# Ucc_28951_Breakout.net
KiCad netlist of a schematic drawn in Altium Designer
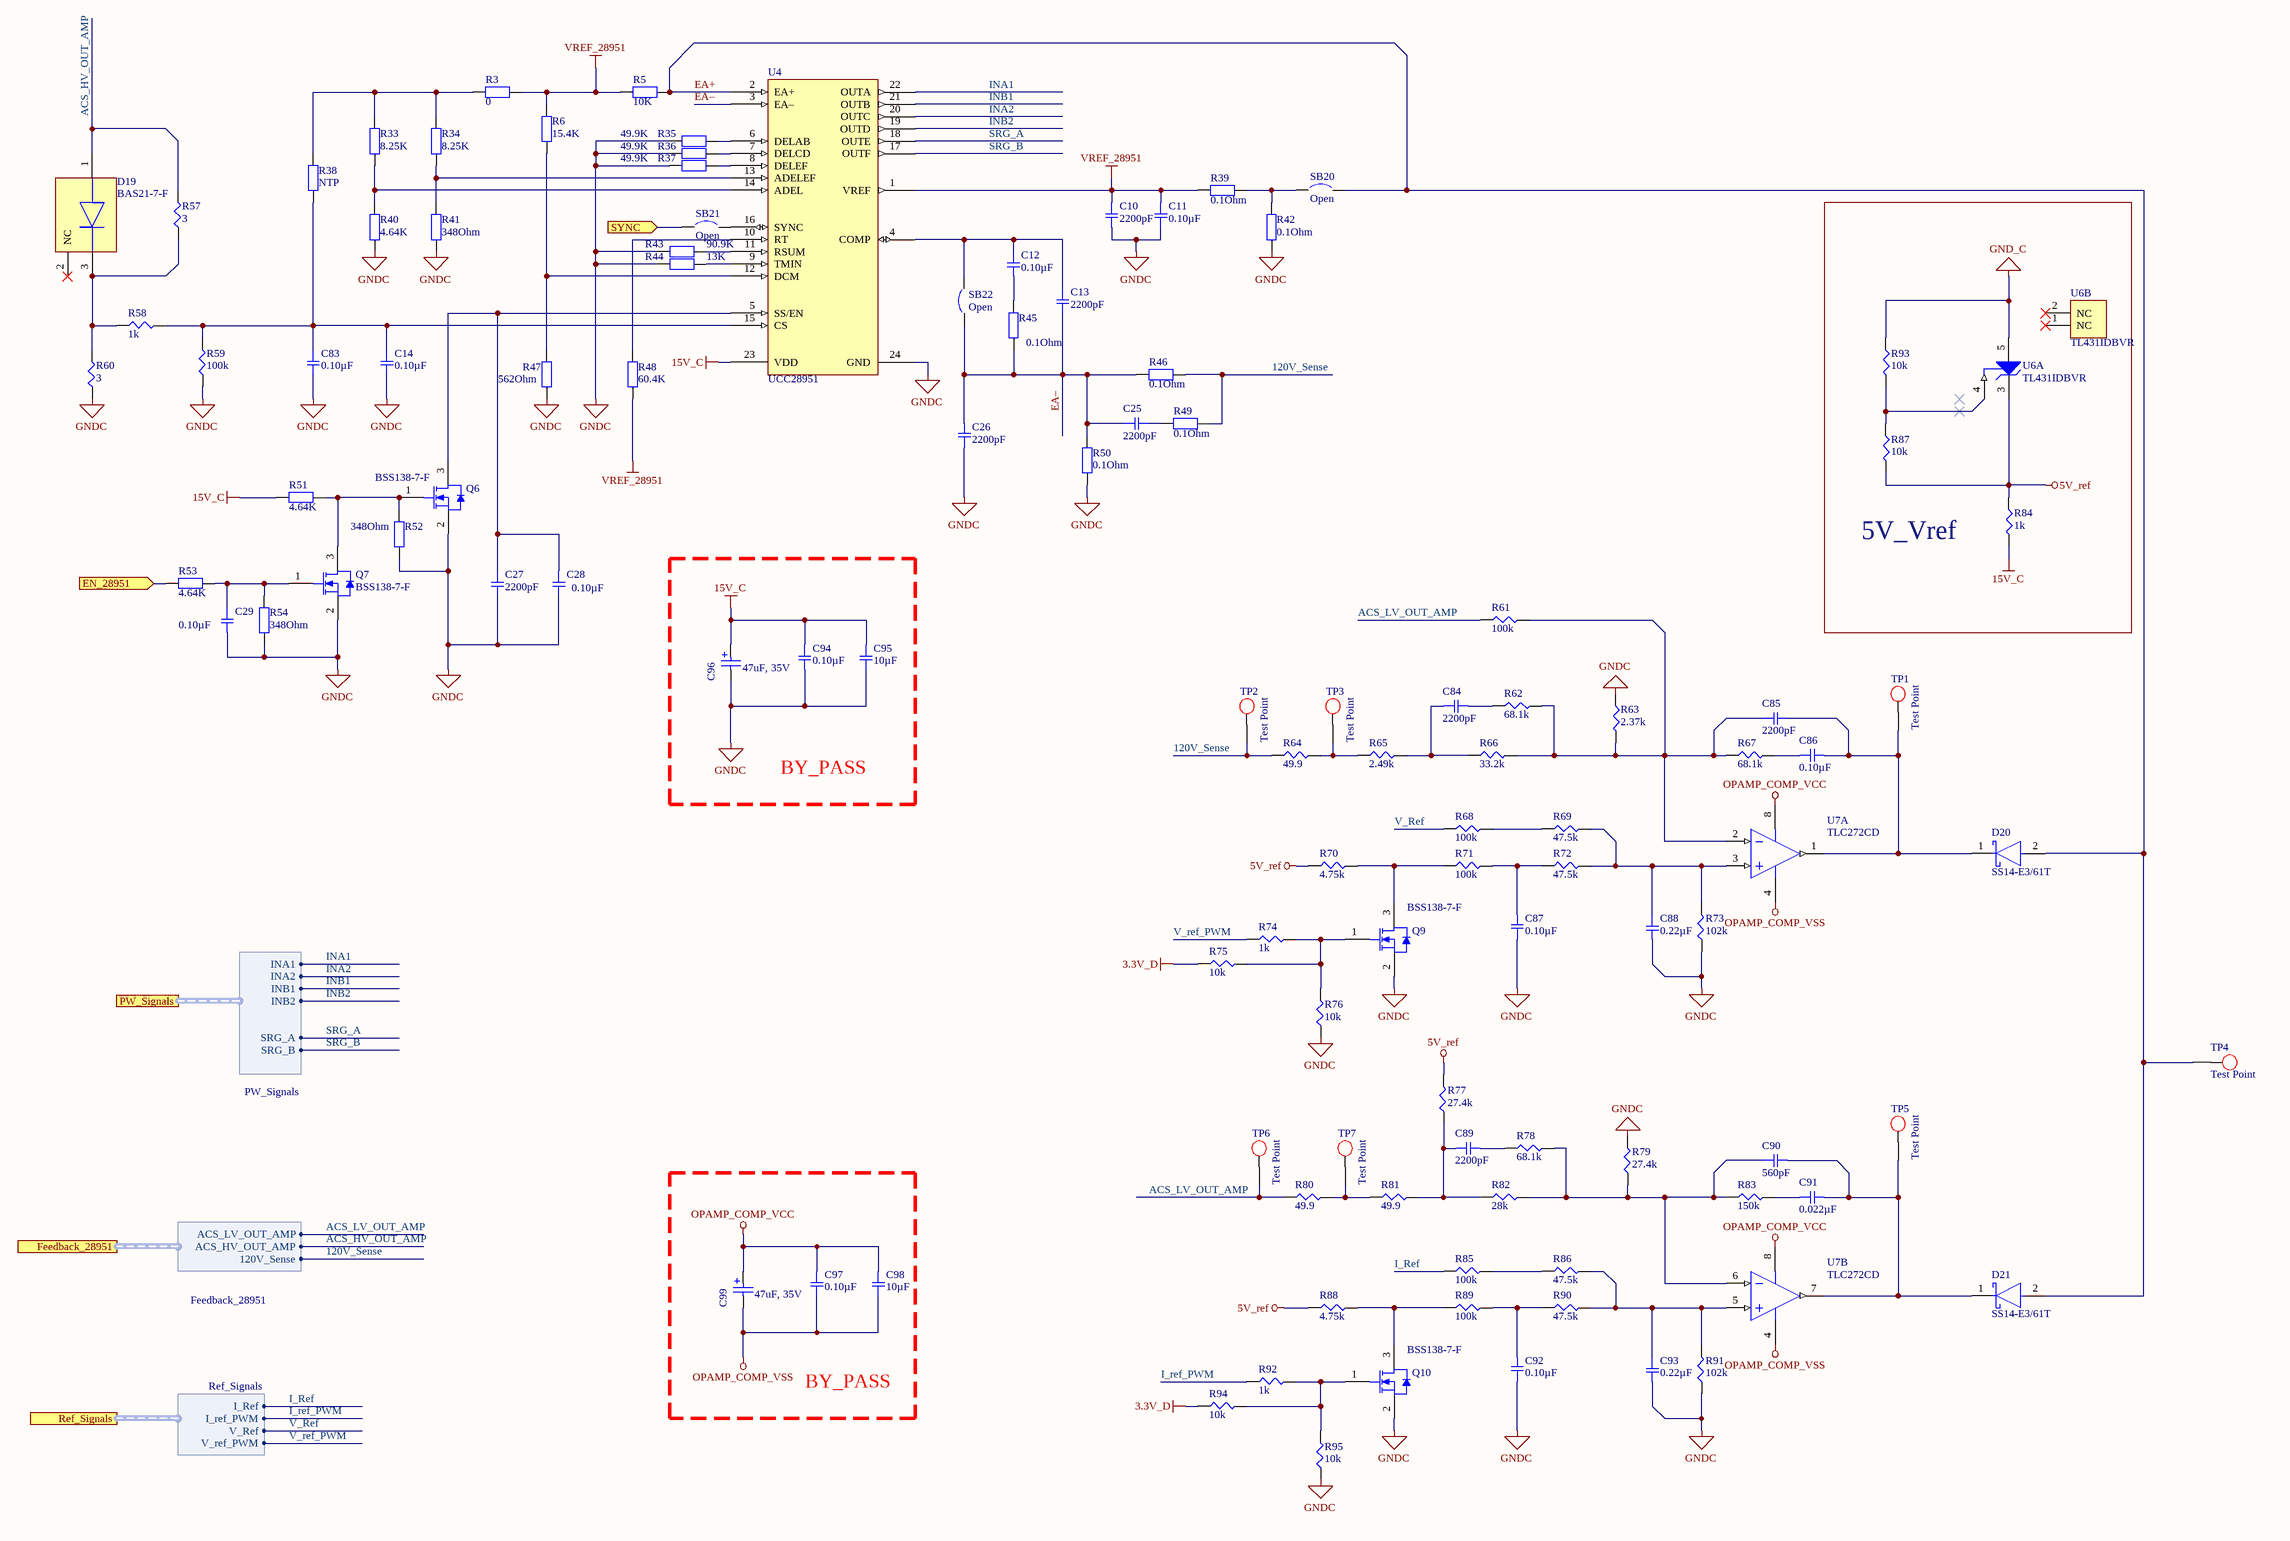
[diagram p0: Ucc_28951_Breakout.SchDoc]

(export (version "E")
  (design (tool "Eeschema 10.0.6"))
  (components
    (comp (ref "C10")
      (value "2200pF")
      (footprint "SMD-0805C")
      (description "CAP CER 2200PF 100V X7R 0805")
      (fields
        (field (name "DIGI-KEY PART NUMBER") "490-6061-1-ND")
        (field (name "PART NUMBER") "GCM216R72A222KA37D")
      )
      (libsource (lib "capacitor_murata_0805") (part "GCM216R72A222KA37D"))
    )
    (comp (ref "C11")
      (value "0.10µF")
      (footprint "SMD-0805C")
      (description "CAP CER 0.1UF 50V X7R 0805")
      (fields
        (field (name "DIGI-KEY PART NUMBER") "490-11955-1-ND")
        (field (name "PART NUMBER") "GCD21BR71H104KA01L")
      )
      (libsource (lib "capacitor_murata_0805") (part "GCD21BR71H104KA01L"))
    )
    (comp (ref "C12")
      (value "0.10µF")
      (footprint "SMD-0805C")
      (description "CAP CER 0.1UF 50V X7R 0805")
      (fields
        (field (name "DIGI-KEY PART NUMBER") "490-11955-1-ND")
        (field (name "PART NUMBER") "GCD21BR71H104KA01L")
      )
      (libsource (lib "capacitor_murata_0805") (part "GCD21BR71H104KA01L"))
    )
    (comp (ref "C13")
      (value "2200pF")
      (footprint "SMD-0805C")
      (description "CAP CER 2200PF 100V X7R 0805")
      (fields
        (field (name "DIGI-KEY PART NUMBER") "490-6061-1-ND")
        (field (name "PART NUMBER") "GCM216R72A222KA37D")
      )
      (libsource (lib "capacitor_murata_0805") (part "GCM216R72A222KA37D"))
    )
    (comp (ref "C14")
      (value "0.10µF")
      (footprint "SMD-0805C")
      (description "CAP CER 0.1UF 50V X7R 0805")
      (fields
        (field (name "DIGI-KEY PART NUMBER") "490-11955-1-ND")
        (field (name "PART NUMBER") "GCD21BR71H104KA01L")
      )
      (libsource (lib "capacitor_murata_0805") (part "GCD21BR71H104KA01L"))
    )
    (comp (ref "C25")
      (value "2200pF")
      (footprint "SMD-0805C")
      (description "CAP CER 2200PF 100V X7R 0805")
      (fields
        (field (name "DIGI-KEY PART NUMBER") "490-6061-1-ND")
        (field (name "PART NUMBER") "GCM216R72A222KA37D")
      )
      (libsource (lib "capacitor_murata_0805") (part "GCM216R72A222KA37D"))
    )
    (comp (ref "C26")
      (value "2200pF")
      (footprint "SMD-0805C")
      (description "CAP CER 2200PF 100V X7R 0805")
      (fields
        (field (name "DIGI-KEY PART NUMBER") "490-6061-1-ND")
        (field (name "PART NUMBER") "GCM216R72A222KA37D")
      )
      (libsource (lib "capacitor_murata_0805") (part "GCM216R72A222KA37D"))
    )
    (comp (ref "C27")
      (value "2200pF")
      (footprint "SMD-0805C")
      (description "CAP CER 2200PF 100V X7R 0805")
      (fields
        (field (name "DIGI-KEY PART NUMBER") "490-6061-1-ND")
        (field (name "PART NUMBER") "GCM216R72A222KA37D")
      )
      (libsource (lib "capacitor_murata_0805") (part "GCM216R72A222KA37D"))
    )
    (comp (ref "C28")
      (value "0.10µF")
      (footprint "SMD-0805C")
      (description "CAP CER 0.1UF 50V X7R 0805")
      (fields
        (field (name "DIGI-KEY PART NUMBER") "490-11955-1-ND")
        (field (name "PART NUMBER") "GCD21BR71H104KA01L")
      )
      (libsource (lib "capacitor_murata_0805") (part "GCD21BR71H104KA01L"))
    )
    (comp (ref "C29")
      (value "0.10µF")
      (footprint "SMD-0805C")
      (description "CAP CER 0.1UF 50V X7R 0805")
      (fields
        (field (name "DIGI-KEY PART NUMBER") "490-11955-1-ND")
        (field (name "PART NUMBER") "GCD21BR71H104KA01L")
      )
      (libsource (lib "capacitor_murata_0805") (part "GCD21BR71H104KA01L"))
    )
    (comp (ref "C83")
      (value "0.10µF")
      (footprint "SMD-0805C")
      (description "CAP CER 0.1UF 50V X7R 0805")
      (fields
        (field (name "DIGI-KEY PART NUMBER") "490-11955-1-ND")
        (field (name "PART NUMBER") "GCD21BR71H104KA01L")
      )
      (libsource (lib "capacitor_murata_0805") (part "GCD21BR71H104KA01L"))
    )
    (comp (ref "C84")
      (value "2200pF")
      (footprint "SMD-0603C")
      (description "CAP CER 2200PF 50V X7R 0603")
      (fields
        (field (name "DIGI-KEY PART NUMBER") "490-5766-1-ND")
        (field (name "PART NUMBER") "GCJ188R71H222KA01D")
      )
      (libsource (lib "capacitor_murata_0603") (part "GCJ188R71H222KA01D"))
    )
    (comp (ref "C85")
      (value "2200pF")
      (footprint "SMD-0603C")
      (description "CAP CER 2200PF 50V X7R 0603")
      (fields
        (field (name "DIGI-KEY PART NUMBER") "490-5766-1-ND")
        (field (name "PART NUMBER") "GCJ188R71H222KA01D")
      )
      (libsource (lib "capacitor_murata_0603") (part "GCJ188R71H222KA01D"))
    )
    (comp (ref "C86")
      (value "0.10µF")
      (footprint "SMD-0603C")
      (description "CAP CER 0.1UF 16V X7R 0603")
      (fields
        (field (name "DIGI-KEY PART NUMBER") "490-5796-1-ND")
        (field (name "PART NUMBER") "GCJ188R71C104KA01D")
      )
      (libsource (lib "capacitor_murata_0603") (part "GCJ188R71C104KA01D"))
    )
    (comp (ref "C87")
      (value "0.10µF")
      (footprint "SMD-0603C")
      (description "CAP CER 0.1UF 16V X7R 0603")
      (fields
        (field (name "DIGI-KEY PART NUMBER") "490-5796-1-ND")
        (field (name "PART NUMBER") "GCJ188R71C104KA01D")
      )
      (libsource (lib "capacitor_murata_0603") (part "GCJ188R71C104KA01D"))
    )
    (comp (ref "C88")
      (value "0.22µF")
      (footprint "SMD-0603C")
      (description "CAP CER 0.22UF 25V X7R 0603")
      (fields
        (field (name "DIGI-KEY PART NUMBER") "490-5797-1-ND")
        (field (name "PART NUMBER") "GCJ188R71E224KA12D")
      )
      (libsource (lib "capacitor_murata_0603") (part "GCJ188R71E224KA12D"))
    )
    (comp (ref "C89")
      (value "2200pF")
      (footprint "SMD-0603C")
      (description "CAP CER 2200PF 50V X7R 0603")
      (fields
        (field (name "DIGI-KEY PART NUMBER") "490-5766-1-ND")
        (field (name "PART NUMBER") "GCJ188R71H222KA01D")
      )
      (libsource (lib "capacitor_murata_0603") (part "GCJ188R71H222KA01D"))
    )
    (comp (ref "C90")
      (value "560pF")
      (footprint "SMD-0603C")
      (description "CAP CER 560PF 25V NP0 0603")
      (fields
        (field (name "DIGI-KEY PART NUMBER") "490-12711-1-ND")
        (field (name "PART NUMBER") "GRM1885C1E561JA01D")
      )
      (libsource (lib "capacitor_murata_0603") (part "GRM1885C1E561JA01D"))
    )
    (comp (ref "C91")
      (value "0.022µF")
      (footprint "SMD-0603C")
      (description "CAP CER 0.022UF 50V X7R 0603")
      (fields
        (field (name "DIGI-KEY PART NUMBER") "490-5851-1-ND")
        (field (name "PART NUMBER") "GCJ188R71H223KA01D")
      )
      (libsource (lib "capacitor_murata_0603") (part "GCJ188R71H223KA01D"))
    )
    (comp (ref "C92")
      (value "0.10µF")
      (footprint "SMD-0603C")
      (description "CAP CER 0.1UF 16V X7R 0603")
      (fields
        (field (name "DIGI-KEY PART NUMBER") "490-5796-1-ND")
        (field (name "PART NUMBER") "GCJ188R71C104KA01D")
      )
      (libsource (lib "capacitor_murata_0603") (part "GCJ188R71C104KA01D"))
    )
    (comp (ref "C93")
      (value "0.22µF")
      (footprint "SMD-0603C")
      (description "CAP CER 0.22UF 25V X7R 0603")
      (fields
        (field (name "DIGI-KEY PART NUMBER") "490-5797-1-ND")
        (field (name "PART NUMBER") "GCJ188R71E224KA12D")
      )
      (libsource (lib "capacitor_murata_0603") (part "GCJ188R71E224KA12D"))
    )
    (comp (ref "C94")
      (value "0.10µF")
      (footprint "SMD-0805C")
      (description "CAP CER 0.1UF 100V X7R 0805")
      (fields
        (field (name "DIGI-KEY PART NUMBER") "490-5825-1-ND")
        (field (name "PART NUMBER") "GCJ21BR72A104KA01L")
      )
      (libsource (lib "capacitor_murata_0805") (part "GCJ21BR72A104KA01L"))
    )
    (comp (ref "C95")
      (value "10µF")
      (footprint "SMD-0805C")
      (description "CAP CER 10UF 10V X7R 0805")
      (fields
        (field (name "DIGI-KEY PART NUMBER") "490-10674-1-ND")
        (field (name "PART NUMBER") "GCM21BR71A106KE22L")
      )
      (libsource (lib "capacitor_murata_0805") (part "GCM21BR71A106KE22L"))
    )
    (comp (ref "C96")
      (value "47uF, 35V")
      (footprint "WCAP-ASLU_8x6.5")
      (description "WCAP-ASLU Aluminium Electrolytic Capacitors, D8mm x L6.5mm, 47uF, +/-20%, 35VDC")
      (fields (field (name "PART NUMBER") "865090549009") (field (name "PUBLISHER") "Wurth Elektronik"))
      (libsource (lib "Altium_WCAP-ASLU_SMD") (part "865090549009"))
    )
    (comp (ref "C97")
      (value "0.10µF")
      (footprint "SMD-0805C")
      (description "CAP CER 0.1UF 100V X7R 0805")
      (fields
        (field (name "DIGI-KEY PART NUMBER") "490-5825-1-ND")
        (field (name "PART NUMBER") "GCJ21BR72A104KA01L")
      )
      (libsource (lib "capacitor_murata_0805") (part "GCJ21BR72A104KA01L"))
    )
    (comp (ref "C98")
      (value "10µF")
      (footprint "SMD-0805C")
      (description "CAP CER 10UF 10V X7R 0805")
      (fields
        (field (name "DIGI-KEY PART NUMBER") "490-10674-1-ND")
        (field (name "PART NUMBER") "GCM21BR71A106KE22L")
      )
      (libsource (lib "capacitor_murata_0805") (part "GCM21BR71A106KE22L"))
    )
    (comp (ref "C99")
      (value "47uF, 35V")
      (footprint "WCAP-ASLU_8x6.5")
      (description "WCAP-ASLU Aluminium Electrolytic Capacitors, D8mm x L6.5mm, 47uF, +/-20%, 35VDC")
      (fields (field (name "PART NUMBER") "865090549009") (field (name "PUBLISHER") "Wurth Elektronik"))
      (libsource (lib "Altium_WCAP-ASLU_SMD") (part "865090549009"))
    )
    (comp (ref "D19")
      (value "BAS21-7-F")
      (footprint "FP-SOT23-MFG")
      (description "DIODE GEN PURP 200V 200MA SOT23")
      (fields
        (field (name "OCTOPART") "https://octopart.com/bas21-7-f-diodes+inc.-325943")
        (field (name "MANUFACTURER") "Diodes Inc.")
      )
      (libsource (lib "Altium Content Vault") (part "4e36664258fec53a771a927e3978fea"))
    )
    (comp (ref "D20")
      (value "SS14-E3/61T")
      (footprint "FP-95400-MFG")
      (description "DIODE SCHOTTKY 40V 1A DO214AC")
      (fields
        (field (name "OCTOPART") "https://octopart.com/ss14-e3%2F61t-vishay-39552847")
        (field (name "MANUFACTURER") "Vishay")
      )
      (libsource (lib "Altium Content Vault") (part "1d6ec82d83fb6aee721767c19dac4b9"))
    )
    (comp (ref "D21")
      (value "SS14-E3/61T")
      (footprint "FP-95400-MFG")
      (description "DIODE SCHOTTKY 40V 1A DO214AC")
      (fields
        (field (name "OCTOPART") "https://octopart.com/ss14-e3%2F61t-vishay-39552847")
        (field (name "MANUFACTURER") "Vishay")
      )
      (libsource (lib "Altium Content Vault") (part "1d6ec82d83fb6aee721767c19dac4b9"))
    )
    (comp (ref "Q6")
      (value "BSS138-7-F")
      (footprint "DIOD-SOT23-3_V")
      (description "N-Channel Enhancement Mode Mosfet, 50 V, 0.2 A, -55 to 150 degC, 3-Pin SOT23, RoHS, Tape and Reel")
      (fields (field (name "MANUFACTURER") "Diodes Inc"))
      (libsource (lib "Altium Content Vault") (part "NEMOS-GSD-3"))
    )
    (comp (ref "Q7")
      (value "BSS138-7-F")
      (footprint "DIOD-SOT23-3_V")
      (description "N-Channel Enhancement Mode Mosfet, 50 V, 0.2 A, -55 to 150 degC, 3-Pin SOT23, RoHS, Tape and Reel")
      (fields (field (name "MANUFACTURER") "Diodes Inc"))
      (libsource (lib "Altium Content Vault") (part "NEMOS-GSD-3"))
    )
    (comp (ref "Q9")
      (value "BSS138-7-F")
      (footprint "DIOD-SOT23-3_V")
      (description "N-Channel Enhancement Mode Mosfet, 50 V, 0.2 A, -55 to 150 degC, 3-Pin SOT23, RoHS, Tape and Reel")
      (fields (field (name "MANUFACTURER") "Diodes Inc"))
      (libsource (lib "Altium Content Vault") (part "NEMOS-GSD-3"))
    )
    (comp (ref "Q10")
      (value "BSS138-7-F")
      (footprint "DIOD-SOT23-3_V")
      (description "N-Channel Enhancement Mode Mosfet, 50 V, 0.2 A, -55 to 150 degC, 3-Pin SOT23, RoHS, Tape and Reel")
      (fields (field (name "MANUFACTURER") "Diodes Inc"))
      (libsource (lib "Altium Content Vault") (part "NEMOS-GSD-3"))
    )
    (comp (ref "R3")
      (value "0")
      (footprint "WRIS-KSKE_0603_H=0.45mm")
      (description "WRIS-KSKE Thick Film Resistors, size 0603, 0.1Ohm, +/-1%, 0.25W")
      (fields (field (name "PART NUMBER") "560050316001") (field (name "PUBLISHER") "Wurth Elektronik"))
      (libsource (lib "") (part "560050316001_1"))
    )
    (comp (ref "R5")
      (value "10K")
      (footprint "WRIS-KSKE_0603_H=0.45mm")
      (description "WRIS-KSKE Thick Film Resistors, size 0603, 0.1Ohm, +/-1%, 0.25W")
      (fields (field (name "PART NUMBER") "560050316001") (field (name "PUBLISHER") "Wurth Elektronik"))
      (libsource (lib "") (part "560050316001_1"))
    )
    (comp (ref "R6")
      (value "15.4K")
      (footprint "WRIS-KSKE_0603_H=0.45mm")
      (description "WRIS-KSKE Thick Film Resistors, size 0603, 0.1Ohm, +/-1%, 0.25W")
      (fields (field (name "PART NUMBER") "560050316001") (field (name "PUBLISHER") "Wurth Elektronik"))
      (libsource (lib "Altium_WRIS-KSKE_rev19a") (part "560050316001"))
    )
    (comp (ref "R33")
      (value "8.25K")
      (footprint "WRIS-KSKE_0603_H=0.45mm")
      (description "WRIS-KSKE Thick Film Resistors, size 0603, 0.1Ohm, +/-1%, 0.25W")
      (fields (field (name "PART NUMBER") "560050316001") (field (name "PUBLISHER") "Wurth Elektronik"))
      (libsource (lib "Altium_WRIS-KSKE_rev19a") (part "560050316001"))
    )
    (comp (ref "R34")
      (value "8.25K")
      (footprint "WRIS-KSKE_0603_H=0.45mm")
      (description "WRIS-KSKE Thick Film Resistors, size 0603, 0.1Ohm, +/-1%, 0.25W")
      (fields (field (name "PART NUMBER") "560050316001") (field (name "PUBLISHER") "Wurth Elektronik"))
      (libsource (lib "Altium_WRIS-KSKE_rev19a") (part "560050316001"))
    )
    (comp (ref "R35")
      (value "49.9K")
      (footprint "WRIS-KSKE_0603_H=0.45mm")
      (description "WRIS-KSKE Thick Film Resistors, size 0603, 0.1Ohm, +/-1%, 0.25W")
      (fields (field (name "PART NUMBER") "560050316001") (field (name "PUBLISHER") "Wurth Elektronik"))
      (libsource (lib "") (part "560050316001_1"))
    )
    (comp (ref "R36")
      (value "49.9K")
      (footprint "WRIS-KSKE_0603_H=0.45mm")
      (description "WRIS-KSKE Thick Film Resistors, size 0603, 0.1Ohm, +/-1%, 0.25W")
      (fields (field (name "PART NUMBER") "560050316001") (field (name "PUBLISHER") "Wurth Elektronik"))
      (libsource (lib "") (part "560050316001_1"))
    )
    (comp (ref "R37")
      (value "49.9K")
      (footprint "WRIS-KSKE_0603_H=0.45mm")
      (description "WRIS-KSKE Thick Film Resistors, size 0603, 0.1Ohm, +/-1%, 0.25W")
      (fields (field (name "PART NUMBER") "560050316001") (field (name "PUBLISHER") "Wurth Elektronik"))
      (libsource (lib "") (part "560050316001_1"))
    )
    (comp (ref "R38")
      (value "NTP")
      (footprint "WRIS-KSKE_0603_H=0.45mm")
      (description "WRIS-KSKE Thick Film Resistors, size 0603, 0.1Ohm, +/-1%, 0.25W")
      (fields (field (name "PART NUMBER") "560050316001") (field (name "PUBLISHER") "Wurth Elektronik"))
      (libsource (lib "Altium_WRIS-KSKE_rev19a") (part "560050316001"))
    )
    (comp (ref "R39")
      (value "0.1Ohm")
      (footprint "WRIS-KSKE_0603_H=0.45mm")
      (description "WRIS-KSKE Thick Film Resistors, size 0603, 0.1Ohm, +/-1%, 0.25W")
      (fields (field (name "PART NUMBER") "560050316001") (field (name "PUBLISHER") "Wurth Elektronik"))
      (libsource (lib "") (part "560050316001_2"))
    )
    (comp (ref "R40")
      (value "4.64K")
      (footprint "WRIS-KSKE_0603_H=0.45mm")
      (description "WRIS-KSKE Thick Film Resistors, size 0603, 0.1Ohm, +/-1%, 0.25W")
      (fields (field (name "PART NUMBER") "560050316001") (field (name "PUBLISHER") "Wurth Elektronik"))
      (libsource (lib "Altium_WRIS-KSKE_rev19a") (part "560050316001"))
    )
    (comp (ref "R41")
      (value "348Ohm")
      (footprint "WRIS-KSKE_0603_H=0.45mm")
      (description "WRIS-KSKE Thick Film Resistors, size 0603, 0.1Ohm, +/-1%, 0.25W")
      (fields (field (name "PART NUMBER") "560050316001") (field (name "PUBLISHER") "Wurth Elektronik"))
      (libsource (lib "Altium_WRIS-KSKE_rev19a") (part "560050316001"))
    )
    (comp (ref "R42")
      (value "0.1Ohm")
      (footprint "WRIS-KSKE_0603_H=0.45mm")
      (description "WRIS-KSKE Thick Film Resistors, size 0603, 0.1Ohm, +/-1%, 0.25W")
      (fields (field (name "PART NUMBER") "560050316001") (field (name "PUBLISHER") "Wurth Elektronik"))
      (libsource (lib "Altium_WRIS-KSKE_rev19a") (part "560050316001"))
    )
    (comp (ref "R43")
      (value "90.9K")
      (footprint "WRIS-KSKE_0603_H=0.45mm")
      (description "WRIS-KSKE Thick Film Resistors, size 0603, 0.1Ohm, +/-1%, 0.25W")
      (fields (field (name "PART NUMBER") "560050316001") (field (name "PUBLISHER") "Wurth Elektronik"))
      (libsource (lib "") (part "560050316001_1"))
    )
    (comp (ref "R44")
      (value "13K")
      (footprint "WRIS-KSKE_0603_H=0.45mm")
      (description "WRIS-KSKE Thick Film Resistors, size 0603, 0.1Ohm, +/-1%, 0.25W")
      (fields (field (name "PART NUMBER") "560050316001") (field (name "PUBLISHER") "Wurth Elektronik"))
      (libsource (lib "") (part "560050316001_1"))
    )
    (comp (ref "R45")
      (value "0.1Ohm")
      (footprint "WRIS-KSKE_0603_H=0.45mm")
      (description "WRIS-KSKE Thick Film Resistors, size 0603, 0.1Ohm, +/-1%, 0.25W")
      (fields (field (name "PART NUMBER") "560050316001") (field (name "PUBLISHER") "Wurth Elektronik"))
      (libsource (lib "") (part "560050316001_3"))
    )
    (comp (ref "R46")
      (value "0.1Ohm")
      (footprint "WRIS-KSKE_0603_H=0.45mm")
      (description "WRIS-KSKE Thick Film Resistors, size 0603, 0.1Ohm, +/-1%, 0.25W")
      (fields (field (name "PART NUMBER") "560050316001") (field (name "PUBLISHER") "Wurth Elektronik"))
      (libsource (lib "") (part "560050316001_1"))
    )
    (comp (ref "R47")
      (value "562Ohm")
      (footprint "WRIS-KSKE_0603_H=0.45mm")
      (description "WRIS-KSKE Thick Film Resistors, size 0603, 0.1Ohm, +/-1%, 0.25W")
      (fields (field (name "PART NUMBER") "560050316001") (field (name "PUBLISHER") "Wurth Elektronik"))
      (libsource (lib "Altium_WRIS-KSKE_rev19a") (part "560050316001"))
    )
    (comp (ref "R48")
      (value "60.4K")
      (footprint "WRIS-KSKE_0603_H=0.45mm")
      (description "WRIS-KSKE Thick Film Resistors, size 0603, 0.1Ohm, +/-1%, 0.25W")
      (fields (field (name "PART NUMBER") "560050316001") (field (name "PUBLISHER") "Wurth Elektronik"))
      (libsource (lib "Altium_WRIS-KSKE_rev19a") (part "560050316001"))
    )
    (comp (ref "R49")
      (value "0.1Ohm")
      (footprint "WRIS-KSKE_0603_H=0.45mm")
      (description "WRIS-KSKE Thick Film Resistors, size 0603, 0.1Ohm, +/-1%, 0.25W")
      (fields (field (name "PART NUMBER") "560050316001") (field (name "PUBLISHER") "Wurth Elektronik"))
      (libsource (lib "") (part "560050316001_1"))
    )
    (comp (ref "R50")
      (value "0.1Ohm")
      (footprint "WRIS-KSKE_0603_H=0.45mm")
      (description "WRIS-KSKE Thick Film Resistors, size 0603, 0.1Ohm, +/-1%, 0.25W")
      (fields (field (name "PART NUMBER") "560050316001") (field (name "PUBLISHER") "Wurth Elektronik"))
      (libsource (lib "Altium_WRIS-KSKE_rev19a") (part "560050316001"))
    )
    (comp (ref "R51")
      (value "4.64K")
      (footprint "WRIS-KSKE_0603_H=0.45mm")
      (description "WRIS-KSKE Thick Film Resistors, size 0603, 0.1Ohm, +/-1%, 0.25W")
      (fields (field (name "PART NUMBER") "560050316001") (field (name "PUBLISHER") "Wurth Elektronik"))
      (libsource (lib "") (part "560050316001_2"))
    )
    (comp (ref "R52")
      (value "348Ohm")
      (footprint "WRIS-KSKE_0603_H=0.45mm")
      (description "WRIS-KSKE Thick Film Resistors, size 0603, 0.1Ohm, +/-1%, 0.25W")
      (fields (field (name "PART NUMBER") "560050316001") (field (name "PUBLISHER") "Wurth Elektronik"))
      (libsource (lib "Altium_WRIS-KSKE_rev19a") (part "560050316001"))
    )
    (comp (ref "R53")
      (value "4.64K")
      (footprint "WRIS-KSKE_0603_H=0.45mm")
      (description "WRIS-KSKE Thick Film Resistors, size 0603, 0.1Ohm, +/-1%, 0.25W")
      (fields (field (name "PART NUMBER") "560050316001") (field (name "PUBLISHER") "Wurth Elektronik"))
      (libsource (lib "") (part "560050316001_2"))
    )
    (comp (ref "R54")
      (value "348Ohm")
      (footprint "WRIS-KSKE_0603_H=0.45mm")
      (description "WRIS-KSKE Thick Film Resistors, size 0603, 0.1Ohm, +/-1%, 0.25W")
      (fields (field (name "PART NUMBER") "560050316001") (field (name "PUBLISHER") "Wurth Elektronik"))
      (libsource (lib "Altium_WRIS-KSKE_rev19a") (part "560050316001"))
    )
    (comp (ref "R57")
      (value "3")
      (footprint "SMD-0603-RES")
      (description "RES SMD 3 OHM 1% 1/4W 0603")
      (fields (field (name "PART NUMBER") "ERJ-3BQF3R0V") (field (name "DIGI-KEY PART NUMBER") "P17381CT-ND"))
      (libsource (lib "Panasonic_ERJ_0603") (part "ERJ-3BQF3R0V"))
    )
    (comp (ref "R58")
      (value "1k")
      (footprint "SMD-0603-RES")
      (description "RES SMD 1K OHM 1% 1/10W 0603")
      (fields
        (field (name "PART NUMBER") "ERJ-3EKF1001V")
        (field (name "DIGI-KEY PART NUMBER") "P1.00KHCT-ND")
      )
      (libsource (lib "Panasonic_ERJ_0603") (part "ERJ-3EKF1001V"))
    )
    (comp (ref "R59")
      (value "100k")
      (footprint "SMD-0603-RES")
      (description "RES SMD 100K OHM 1% 1/10W 0603")
      (fields
        (field (name "PART NUMBER") "ERJ-3EKF1003V")
        (field (name "DIGI-KEY PART NUMBER") "P100KHCT-ND")
      )
      (libsource (lib "Panasonic_ERJ_0603") (part "ERJ-3EKF1003V"))
    )
    (comp (ref "R60")
      (value "3")
      (footprint "SMD-0603-RES")
      (description "RES SMD 3 OHM 1% 1/4W 0603")
      (fields (field (name "PART NUMBER") "ERJ-3BQF3R0V") (field (name "DIGI-KEY PART NUMBER") "P17381CT-ND"))
      (libsource (lib "Panasonic_ERJ_0603") (part "ERJ-3BQF3R0V"))
    )
    (comp (ref "R61")
      (value "100k")
      (footprint "SMD-0603-RES")
      (description "RES SMD 100K OHM 1% 1/10W 0603")
      (fields
        (field (name "PART NUMBER") "ERJ-3EKF1003V")
        (field (name "DIGI-KEY PART NUMBER") "P100KHCT-ND")
      )
      (libsource (lib "Panasonic_ERJ_0603") (part "ERJ-3EKF1003V"))
    )
    (comp (ref "R62")
      (value "68.1k")
      (footprint "SMD-0603-RES")
      (description "RES SMD 68.1K OHM 1% 1/10W 0603")
      (fields
        (field (name "PART NUMBER") "ERJ-3EKF6812V")
        (field (name "DIGI-KEY PART NUMBER") "P68.1KHCT-ND")
      )
      (libsource (lib "Panasonic_ERJ_0603") (part "ERJ-3EKF6812V"))
    )
    (comp (ref "R63")
      (value "2.37k")
      (footprint "SMD-0603-RES")
      (description "RES SMD 2.37K OHM 1% 1/10W 0603")
      (fields
        (field (name "PART NUMBER") "ERJ-3EKF2371V")
        (field (name "DIGI-KEY PART NUMBER") "P2.37KHCT-ND")
      )
      (libsource (lib "Panasonic_ERJ_0603") (part "ERJ-3EKF2371V"))
    )
    (comp (ref "R64")
      (value "49.9")
      (footprint "SMD-0603-RES")
      (description "RES SMD 49.9 OHM 1% 1/10W 0603")
      (fields
        (field (name "PART NUMBER") "ERJ-3EKF49R9V")
        (field (name "DIGI-KEY PART NUMBER") "P49.9HCT-ND")
      )
      (libsource (lib "Panasonic_ERJ_0603") (part "ERJ-3EKF49R9V"))
    )
    (comp (ref "R65")
      (value "2.49k")
      (footprint "SMD-0603-RES")
      (description "RES SMD 2.49K OHM 1% 1/10W 0603")
      (fields
        (field (name "PART NUMBER") "ERJ-3EKF2491V")
        (field (name "DIGI-KEY PART NUMBER") "P2.49KHCT-ND")
      )
      (libsource (lib "Panasonic_ERJ_0603") (part "ERJ-3EKF2491V"))
    )
    (comp (ref "R66")
      (value "33.2k")
      (footprint "SMD-0603-RES")
      (description "RES SMD 33.2K OHM 1% 1/10W 0603")
      (fields
        (field (name "PART NUMBER") "ERJ-3EKF3322V")
        (field (name "DIGI-KEY PART NUMBER") "P33.2KHCT-ND")
      )
      (libsource (lib "Panasonic_ERJ_0603") (part "ERJ-3EKF3322V"))
    )
    (comp (ref "R67")
      (value "68.1k")
      (footprint "SMD-0603-RES")
      (description "RES SMD 68.1K OHM 1% 1/10W 0603")
      (fields
        (field (name "PART NUMBER") "ERJ-3EKF6812V")
        (field (name "DIGI-KEY PART NUMBER") "P68.1KHCT-ND")
      )
      (libsource (lib "Panasonic_ERJ_0603") (part "ERJ-3EKF6812V"))
    )
    (comp (ref "R68")
      (value "100k")
      (footprint "SMD-0603-RES")
      (description "RES SMD 100K OHM 1% 1/10W 0603")
      (fields
        (field (name "PART NUMBER") "ERJ-3EKF1003V")
        (field (name "DIGI-KEY PART NUMBER") "P100KHCT-ND")
      )
      (libsource (lib "Panasonic_ERJ_0603") (part "ERJ-3EKF1003V"))
    )
    (comp (ref "R69")
      (value "47.5k")
      (footprint "SMD-0603-RES")
      (description "RES SMD 47.5K OHM 1% 1/10W 0603")
      (fields
        (field (name "PART NUMBER") "ERJ-3EKF4752V")
        (field (name "DIGI-KEY PART NUMBER") "P47.5KHCT-ND")
      )
      (libsource (lib "Panasonic_ERJ_0603") (part "ERJ-3EKF4752V"))
    )
    (comp (ref "R70")
      (value "4.75k")
      (footprint "SMD-0603-RES")
      (description "RES SMD 4.75K OHM 1% 1/10W 0603")
      (fields
        (field (name "PART NUMBER") "ERJ-3EKF4751V")
        (field (name "DIGI-KEY PART NUMBER") "P4.75KHCT-ND")
      )
      (libsource (lib "Panasonic_ERJ_0603") (part "ERJ-3EKF4751V"))
    )
    (comp (ref "R71")
      (value "100k")
      (footprint "SMD-0603-RES")
      (description "RES SMD 100K OHM 1% 1/10W 0603")
      (fields
        (field (name "PART NUMBER") "ERJ-3EKF1003V")
        (field (name "DIGI-KEY PART NUMBER") "P100KHCT-ND")
      )
      (libsource (lib "Panasonic_ERJ_0603") (part "ERJ-3EKF1003V"))
    )
    (comp (ref "R72")
      (value "47.5k")
      (footprint "SMD-0603-RES")
      (description "RES SMD 47.5K OHM 1% 1/10W 0603")
      (fields
        (field (name "PART NUMBER") "ERJ-3EKF4752V")
        (field (name "DIGI-KEY PART NUMBER") "P47.5KHCT-ND")
      )
      (libsource (lib "Panasonic_ERJ_0603") (part "ERJ-3EKF4752V"))
    )
    (comp (ref "R73")
      (value "102k")
      (footprint "SMD-0603-RES")
      (description "RES SMD 102K OHM 1% 1/10W 0603")
      (fields
        (field (name "PART NUMBER") "ERJ-3EKF1023V")
        (field (name "DIGI-KEY PART NUMBER") "P102KHCT-ND")
      )
      (libsource (lib "Panasonic_ERJ_0603") (part "ERJ-3EKF1023V"))
    )
    (comp (ref "R74")
      (value "1k")
      (footprint "SMD-0603-RES")
      (description "RES SMD 1K OHM 1% 1/10W 0603")
      (fields
        (field (name "PART NUMBER") "ERJ-3EKF1001V")
        (field (name "DIGI-KEY PART NUMBER") "P1.00KHCT-ND")
      )
      (libsource (lib "Panasonic_ERJ_0603") (part "ERJ-3EKF1001V"))
    )
    (comp (ref "R75")
      (value "10k")
      (footprint "SMD-0603-RES")
      (description "RES SMD 10K OHM 1% 1/10W 0603")
      (fields
        (field (name "PART NUMBER") "ERJ-3EKF1002V")
        (field (name "DIGI-KEY PART NUMBER") "P10.0KHCT-ND")
      )
      (libsource (lib "Panasonic_ERJ_0603") (part "ERJ-3EKF1002V"))
    )
    (comp (ref "R76")
      (value "10k")
      (footprint "SMD-0603-RES")
      (description "RES SMD 10K OHM 1% 1/10W 0603")
      (fields
        (field (name "PART NUMBER") "ERJ-3EKF1002V")
        (field (name "DIGI-KEY PART NUMBER") "P10.0KHCT-ND")
      )
      (libsource (lib "Panasonic_ERJ_0603") (part "ERJ-3EKF1002V"))
    )
    (comp (ref "R77")
      (value "27.4k")
      (footprint "SMD-0603-RES")
      (description "RES SMD 27.4K OHM 1% 1/10W 0603")
      (fields
        (field (name "PART NUMBER") "ERJ-3EKF2742V")
        (field (name "DIGI-KEY PART NUMBER") "P27.4KHCT-ND")
      )
      (libsource (lib "Panasonic_ERJ_0603") (part "ERJ-3EKF2742V"))
    )
    (comp (ref "R78")
      (value "68.1k")
      (footprint "SMD-0603-RES")
      (description "RES SMD 68.1K OHM 1% 1/10W 0603")
      (fields
        (field (name "PART NUMBER") "ERJ-3EKF6812V")
        (field (name "DIGI-KEY PART NUMBER") "P68.1KHCT-ND")
      )
      (libsource (lib "Panasonic_ERJ_0603") (part "ERJ-3EKF6812V"))
    )
    (comp (ref "R79")
      (value "27.4k")
      (footprint "SMD-0603-RES")
      (description "RES SMD 27.4K OHM 1% 1/10W 0603")
      (fields
        (field (name "PART NUMBER") "ERJ-3EKF2742V")
        (field (name "DIGI-KEY PART NUMBER") "P27.4KHCT-ND")
      )
      (libsource (lib "Panasonic_ERJ_0603") (part "ERJ-3EKF2742V"))
    )
    (comp (ref "R80")
      (value "49.9")
      (footprint "SMD-0603-RES")
      (description "RES SMD 49.9 OHM 1% 1/10W 0603")
      (fields
        (field (name "PART NUMBER") "ERJ-3EKF49R9V")
        (field (name "DIGI-KEY PART NUMBER") "P49.9HCT-ND")
      )
      (libsource (lib "Panasonic_ERJ_0603") (part "ERJ-3EKF49R9V"))
    )
    (comp (ref "R81")
      (value "49.9")
      (footprint "SMD-0603-RES")
      (description "RES SMD 49.9 OHM 1% 1/10W 0603")
      (fields
        (field (name "PART NUMBER") "ERJ-3EKF49R9V")
        (field (name "DIGI-KEY PART NUMBER") "P49.9HCT-ND")
      )
      (libsource (lib "Panasonic_ERJ_0603") (part "ERJ-3EKF49R9V"))
    )
    (comp (ref "R82")
      (value "28k")
      (footprint "SMD-0603-RES")
      (description "RES SMD 28K OHM 1% 1/10W 0603")
      (fields
        (field (name "PART NUMBER") "ERJ-3EKF2802V")
        (field (name "DIGI-KEY PART NUMBER") "P28.0KHCT-ND")
      )
      (libsource (lib "Panasonic_ERJ_0603") (part "ERJ-3EKF2802V"))
    )
    (comp (ref "R83")
      (value "150k")
      (footprint "SMD-0603-RES")
      (description "RES SMD 150K OHM 1% 1/10W 0603")
      (fields
        (field (name "PART NUMBER") "ERJ-3EKF1503V")
        (field (name "DIGI-KEY PART NUMBER") "P150KHCT-ND")
      )
      (libsource (lib "Panasonic_ERJ_0603") (part "ERJ-3EKF1503V"))
    )
    (comp (ref "R84")
      (value "1k")
      (footprint "SMD-0603-RES")
      (description "RES SMD 1K OHM 1% 1/10W 0603")
      (fields
        (field (name "PART NUMBER") "ERJ-3EKF1001V")
        (field (name "DIGI-KEY PART NUMBER") "P1.00KHCT-ND")
      )
      (libsource (lib "Panasonic_ERJ_0603") (part "ERJ-3EKF1001V"))
    )
    (comp (ref "R85")
      (value "100k")
      (footprint "SMD-0603-RES")
      (description "RES SMD 100K OHM 1% 1/10W 0603")
      (fields
        (field (name "PART NUMBER") "ERJ-3EKF1003V")
        (field (name "DIGI-KEY PART NUMBER") "P100KHCT-ND")
      )
      (libsource (lib "Panasonic_ERJ_0603") (part "ERJ-3EKF1003V"))
    )
    (comp (ref "R86")
      (value "47.5k")
      (footprint "SMD-0603-RES")
      (description "RES SMD 47.5K OHM 1% 1/10W 0603")
      (fields
        (field (name "PART NUMBER") "ERJ-3EKF4752V")
        (field (name "DIGI-KEY PART NUMBER") "P47.5KHCT-ND")
      )
      (libsource (lib "Panasonic_ERJ_0603") (part "ERJ-3EKF4752V"))
    )
    (comp (ref "R87")
      (value "10k")
      (footprint "SMD-0603-RES")
      (description "RES SMD 10K OHM 1% 1/10W 0603")
      (fields
        (field (name "PART NUMBER") "ERJ-3EKF1002V")
        (field (name "DIGI-KEY PART NUMBER") "P10.0KHCT-ND")
      )
      (libsource (lib "Panasonic_ERJ_0603") (part "ERJ-3EKF1002V"))
    )
    (comp (ref "R88")
      (value "4.75k")
      (footprint "SMD-0603-RES")
      (description "RES SMD 4.75K OHM 1% 1/10W 0603")
      (fields
        (field (name "PART NUMBER") "ERJ-3EKF4751V")
        (field (name "DIGI-KEY PART NUMBER") "P4.75KHCT-ND")
      )
      (libsource (lib "Panasonic_ERJ_0603") (part "ERJ-3EKF4751V"))
    )
    (comp (ref "R89")
      (value "100k")
      (footprint "SMD-0603-RES")
      (description "RES SMD 100K OHM 1% 1/10W 0603")
      (fields
        (field (name "PART NUMBER") "ERJ-3EKF1003V")
        (field (name "DIGI-KEY PART NUMBER") "P100KHCT-ND")
      )
      (libsource (lib "Panasonic_ERJ_0603") (part "ERJ-3EKF1003V"))
    )
    (comp (ref "R90")
      (value "47.5k")
      (footprint "SMD-0603-RES")
      (description "RES SMD 47.5K OHM 1% 1/10W 0603")
      (fields
        (field (name "PART NUMBER") "ERJ-3EKF4752V")
        (field (name "DIGI-KEY PART NUMBER") "P47.5KHCT-ND")
      )
      (libsource (lib "Panasonic_ERJ_0603") (part "ERJ-3EKF4752V"))
    )
    (comp (ref "R91")
      (value "102k")
      (footprint "SMD-0603-RES")
      (description "RES SMD 102K OHM 1% 1/10W 0603")
      (fields
        (field (name "PART NUMBER") "ERJ-3EKF1023V")
        (field (name "DIGI-KEY PART NUMBER") "P102KHCT-ND")
      )
      (libsource (lib "Panasonic_ERJ_0603") (part "ERJ-3EKF1023V"))
    )
    (comp (ref "R92")
      (value "1k")
      (footprint "SMD-0603-RES")
      (description "RES SMD 1K OHM 1% 1/10W 0603")
      (fields
        (field (name "PART NUMBER") "ERJ-3EKF1001V")
        (field (name "DIGI-KEY PART NUMBER") "P1.00KHCT-ND")
      )
      (libsource (lib "Panasonic_ERJ_0603") (part "ERJ-3EKF1001V"))
    )
    (comp (ref "R93")
      (value "10k")
      (footprint "SMD-0603-RES")
      (description "RES SMD 10K OHM 1% 1/10W 0603")
      (fields
        (field (name "PART NUMBER") "ERJ-3EKF1002V")
        (field (name "DIGI-KEY PART NUMBER") "P10.0KHCT-ND")
      )
      (libsource (lib "Panasonic_ERJ_0603") (part "ERJ-3EKF1002V"))
    )
    (comp (ref "R94")
      (value "10k")
      (footprint "SMD-0603-RES")
      (description "RES SMD 10K OHM 1% 1/10W 0603")
      (fields
        (field (name "PART NUMBER") "ERJ-3EKF1002V")
        (field (name "DIGI-KEY PART NUMBER") "P10.0KHCT-ND")
      )
      (libsource (lib "Panasonic_ERJ_0603") (part "ERJ-3EKF1002V"))
    )
    (comp (ref "R95")
      (value "10k")
      (footprint "SMD-0603-RES")
      (description "RES SMD 10K OHM 1% 1/10W 0603")
      (fields
        (field (name "PART NUMBER") "ERJ-3EKF1002V")
        (field (name "DIGI-KEY PART NUMBER") "P10.0KHCT-ND")
      )
      (libsource (lib "Panasonic_ERJ_0603") (part "ERJ-3EKF1002V"))
    )
    (comp (ref "SB20")
      (value "Open")
      (footprint "SB_0603")
      (description "Circuit Breaker")
      (fields (field (name "PUBLISHER") "Altium Limited"))
      (libsource (lib "Edge_Card_Ucc28951") (part "Solder Bridge"))
    )
    (comp (ref "SB21")
      (value "Open")
      (footprint "SB_0603")
      (description "Circuit Breaker")
      (fields (field (name "PUBLISHER") "Altium Limited"))
      (libsource (lib "Edge_Card_Ucc28951") (part "Solder Bridge"))
    )
    (comp (ref "SB22")
      (value "Open")
      (footprint "SB_0603")
      (description "Circuit Breaker")
      (fields (field (name "PUBLISHER") "Altium Limited"))
      (libsource (lib "Edge_Card_Ucc28951") (part "Solder Bridge"))
    )
    (comp (ref "TP1")
      (value "Test Point")
      (footprint "Test_point_THT")
      (libsource (lib "Edge_Card_Ucc28951") (part "Test Point"))
    )
    (comp (ref "TP2")
      (value "Test Point")
      (footprint "Test_point_THT")
      (libsource (lib "Edge_Card_Ucc28951") (part "Test Point"))
    )
    (comp (ref "TP3")
      (value "Test Point")
      (footprint "Test_point_THT")
      (libsource (lib "Edge_Card_Ucc28951") (part "Test Point"))
    )
    (comp (ref "TP4")
      (value "Test Point")
      (footprint "Test_point_THT")
      (libsource (lib "Edge_Card_Ucc28951") (part "Test Point"))
    )
    (comp (ref "TP5")
      (value "Test Point")
      (footprint "Test_point_THT")
      (libsource (lib "Edge_Card_Ucc28951") (part "Test Point"))
    )
    (comp (ref "TP6")
      (value "Test Point")
      (footprint "Test_point_THT")
      (libsource (lib "Edge_Card_Ucc28951") (part "Test Point"))
    )
    (comp (ref "TP7")
      (value "Test Point")
      (footprint "Test_point_THT")
      (libsource (lib "Edge_Card_Ucc28951") (part "Test Point"))
    )
    (comp (ref "U4")
      (value "UCC28951")
      (footprint "TSOP65P640X120_HS-25N")
      (description "UCC28951 Phase-Shifted Full-Bridge Controller\r\nfor Wide Input-Voltage Range Applications")
      (libsource (lib "Edge_Card_Ucc28951") (part "CMP-0000-28951-2"))
    )
    (comp (ref "U6")
      (value "TL431IDBVR")
      (footprint "DBV0005A_M")
      (fields (field (name "MANUFACTURER") "Texas Instruments"))
      (libsource (lib "") (part "TI-TL431DBV5_1"))
    )
    (comp (ref "U7")
      (value "TLC272CD")
      (footprint "D0008A_N")
      (fields (field (name "MANUFACTURER") "Texas Instruments"))
      (libsource (lib "Altium Content Vault") (part "TI-TLC272X-P_D8"))
    )
  )
  (nets
    (net (code "4") (name "/120V_Sense") (class "Default")
      (node (ref "R46") (pin "1") (pinfunction "1_1") (pintype "passive"))
      (node (ref "R49") (pin "1") (pinfunction "1_1") (pintype "passive"))
      (node (ref "R64") (pin "1") (pinfunction "1_1") (pintype "passive"))
      (node (ref "TP2") (pin "1") (pinfunction "1_1") (pintype "passive"))
    )
    (net (code "5") (name "/ACS_HV_OUT_AMP") (class "Default")
      (node (ref "D19") (pin "1") (pinfunction "A_1") (pintype "passive"))
      (node (ref "R57") (pin "2") (pinfunction "2_2") (pintype "passive"))
    )
    (net (code "6") (name "/ACS_LV_OUT_AMP") (class "Default")
      (node (ref "R61") (pin "1") (pinfunction "1_1") (pintype "passive"))
      (node (ref "R80") (pin "1") (pinfunction "1_1") (pintype "passive"))
      (node (ref "TP6") (pin "1") (pinfunction "1_1") (pintype "passive"))
    )
    (net (code "7") (name "/EA+") (class "Default")
      (node (ref "D20") (pin "2") (pinfunction "A_2") (pintype "passive"))
      (node (ref "D21") (pin "2") (pinfunction "A_2") (pintype "passive"))
      (node (ref "R5") (pin "1") (pinfunction "1_1") (pintype "passive"))
      (node (ref "SB20") (pin "2") (pinfunction "2_2") (pintype "passive"))
      (node (ref "TP4") (pin "1") (pinfunction "1_1") (pintype "passive"))
      (node (ref "U4") (pin "2") (pinfunction "EA+_2") (pintype "input"))
    )
    (net (code "8") (name "/EA–") (class "Default")
      (node (ref "C13") (pin "2") (pinfunction "2_2") (pintype "passive"))
      (node (ref "C25") (pin "1") (pinfunction "1_1") (pintype "passive"))
      (node (ref "C26") (pin "2") (pinfunction "2_2") (pintype "passive"))
      (node (ref "R45") (pin "1") (pinfunction "1_1") (pintype "passive"))
      (node (ref "R46") (pin "2") (pinfunction "2_2") (pintype "passive"))
      (node (ref "R50") (pin "1") (pinfunction "1_1") (pintype "passive"))
      (node (ref "SB22") (pin "1") (pinfunction "1_1") (pintype "passive"))
      (node (ref "U4") (pin "3") (pinfunction "EA–_3") (pintype "input"))
    )
    (net (code "9") (name "/EN_28951") (class "Default")
      (node (ref "R53") (pin "1") (pinfunction "1_1") (pintype "passive"))
    )
    (net (code "10") (name "/INA1") (class "Default")
      (node (ref "U4") (pin "22") (pinfunction "OUTA_22") (pintype "output"))
    )
    (net (code "11") (name "/INA2") (class "Default")
      (node (ref "U4") (pin "20") (pinfunction "OUTC_20") (pintype "output"))
    )
    (net (code "12") (name "/INB1") (class "Default")
      (node (ref "U4") (pin "21") (pinfunction "OUTB_21") (pintype "output"))
    )
    (net (code "13") (name "/INB2") (class "Default")
      (node (ref "U4") (pin "19") (pinfunction "OUTD_19") (pintype "output"))
    )
    (net (code "14") (name "/I_Ref") (class "Default")
      (node (ref "R85") (pin "1") (pinfunction "1_1") (pintype "passive"))
    )
    (net (code "15") (name "/I_ref_PWM") (class "Default")
      (node (ref "R92") (pin "1") (pinfunction "1_1") (pintype "passive"))
    )
    (net (code "16") (name "/SRG_A") (class "Default")
      (node (ref "U4") (pin "18") (pinfunction "OUTE_18") (pintype "output"))
    )
    (net (code "17") (name "/SRG_B") (class "Default")
      (node (ref "U4") (pin "17") (pinfunction "OUTF_17") (pintype "output"))
    )
    (net (code "18") (name "/SYNC") (class "Default")
      (node (ref "SB21") (pin "1") (pinfunction "1_1") (pintype "passive"))
    )
    (net (code "19") (name "/V_Ref") (class "Default")
      (node (ref "R68") (pin "1") (pinfunction "1_1") (pintype "passive"))
    )
    (net (code "20") (name "/V_ref_PWM") (class "Default")
      (node (ref "R74") (pin "1") (pinfunction "1_1") (pintype "passive"))
    )
    (net (code "24") (name "3.3V_D") (class "Default")
      (node (ref "R75") (pin "1") (pinfunction "1_1") (pintype "passive"))
      (node (ref "R94") (pin "1") (pinfunction "1_1") (pintype "passive"))
    )
    (net (code "25") (name "5V_ref") (class "Default")
      (node (ref "R70") (pin "1") (pinfunction "1_1") (pintype "passive"))
      (node (ref "R77") (pin "2") (pinfunction "2_2") (pintype "passive"))
      (node (ref "R84") (pin "1") (pinfunction "1_1") (pintype "passive"))
      (node (ref "R87") (pin "2") (pinfunction "2_2") (pintype "passive"))
      (node (ref "R88") (pin "1") (pinfunction "1_1") (pintype "passive"))
      (node (ref "U6") (pin "3") (pinfunction "CATHODE_3") (pintype "passive"))
    )
    (net (code "26") (name "15V_C") (class "Default")
      (node (ref "C94") (pin "1") (pinfunction "1_1") (pintype "passive"))
      (node (ref "C95") (pin "1") (pinfunction "1_1") (pintype "passive"))
      (node (ref "C96") (pin "2") (pinfunction "P_2") (pintype "passive"))
      (node (ref "R51") (pin "1") (pinfunction "1_1") (pintype "passive"))
      (node (ref "R84") (pin "2") (pinfunction "2_2") (pintype "passive"))
      (node (ref "U4") (pin "23") (pinfunction "VDD_23") (pintype "power_in"))
    )
    (net (code "27") (name "GNDC") (class "Default")
      (node (ref "C10") (pin "2") (pinfunction "2_2") (pintype "passive"))
      (node (ref "C11") (pin "2") (pinfunction "2_2") (pintype "passive"))
      (node (ref "C14") (pin "2") (pinfunction "2_2") (pintype "passive"))
      (node (ref "C26") (pin "1") (pinfunction "1_1") (pintype "passive"))
      (node (ref "C27") (pin "2") (pinfunction "2_2") (pintype "passive"))
      (node (ref "C28") (pin "2") (pinfunction "2_2") (pintype "passive"))
      (node (ref "C29") (pin "2") (pinfunction "2_2") (pintype "passive"))
      (node (ref "C83") (pin "2") (pinfunction "2_2") (pintype "passive"))
      (node (ref "C87") (pin "1") (pinfunction "1_1") (pintype "passive"))
      (node (ref "C88") (pin "2") (pinfunction "2_2") (pintype "passive"))
      (node (ref "C92") (pin "1") (pinfunction "1_1") (pintype "passive"))
      (node (ref "C93") (pin "2") (pinfunction "2_2") (pintype "passive"))
      (node (ref "C94") (pin "2") (pinfunction "2_2") (pintype "passive"))
      (node (ref "C95") (pin "2") (pinfunction "2_2") (pintype "passive"))
      (node (ref "C96") (pin "1") (pinfunction "N_1") (pintype "passive"))
      (node (ref "Q10") (pin "2") (pinfunction "S_2") (pintype "passive"))
      (node (ref "Q6") (pin "2") (pinfunction "S_2") (pintype "passive"))
      (node (ref "Q7") (pin "2") (pinfunction "S_2") (pintype "passive"))
      (node (ref "Q9") (pin "2") (pinfunction "S_2") (pintype "passive"))
      (node (ref "R35") (pin "2") (pinfunction "2_2") (pintype "passive"))
      (node (ref "R36") (pin "2") (pinfunction "2_2") (pintype "passive"))
      (node (ref "R37") (pin "2") (pinfunction "2_2") (pintype "passive"))
      (node (ref "R40") (pin "2") (pinfunction "2_2") (pintype "passive"))
      (node (ref "R41") (pin "2") (pinfunction "2_2") (pintype "passive"))
      (node (ref "R42") (pin "2") (pinfunction "2_2") (pintype "passive"))
      (node (ref "R43") (pin "2") (pinfunction "2_2") (pintype "passive"))
      (node (ref "R44") (pin "2") (pinfunction "2_2") (pintype "passive"))
      (node (ref "R47") (pin "2") (pinfunction "2_2") (pintype "passive"))
      (node (ref "R50") (pin "2") (pinfunction "2_2") (pintype "passive"))
      (node (ref "R52") (pin "2") (pinfunction "2_2") (pintype "passive"))
      (node (ref "R54") (pin "2") (pinfunction "2_2") (pintype "passive"))
      (node (ref "R59") (pin "1") (pinfunction "1_1") (pintype "passive"))
      (node (ref "R60") (pin "1") (pinfunction "1_1") (pintype "passive"))
      (node (ref "R63") (pin "1") (pinfunction "1_1") (pintype "passive"))
      (node (ref "R73") (pin "1") (pinfunction "1_1") (pintype "passive"))
      (node (ref "R76") (pin "1") (pinfunction "1_1") (pintype "passive"))
      (node (ref "R79") (pin "2") (pinfunction "2_2") (pintype "passive"))
      (node (ref "R91") (pin "1") (pinfunction "1_1") (pintype "passive"))
      (node (ref "R95") (pin "1") (pinfunction "1_1") (pintype "passive"))
      (node (ref "U4") (pin "24") (pinfunction "GND_24") (pintype "power_in"))
    )
    (net (code "28") (name "GND_C") (class "Default")
      (node (ref "R93") (pin "1") (pinfunction "1_1") (pintype "passive"))
      (node (ref "U6") (pin "5") (pinfunction "ANODE_5") (pintype "passive"))
    )
    (net (code "29") (name "Net-(C12-Pad2)") (class "Default")
      (node (ref "C12") (pin "2") (pinfunction "2_2") (pintype "passive"))
      (node (ref "R45") (pin "2") (pinfunction "2_2") (pintype "passive"))
    )
    (net (code "30") (name "Net-(C25-Pad2)") (class "Default")
      (node (ref "C25") (pin "2") (pinfunction "2_2") (pintype "passive"))
      (node (ref "R49") (pin "2") (pinfunction "2_2") (pintype "passive"))
    )
    (net (code "31") (name "Net-(C84-Pad1)") (class "Default")
      (node (ref "C84") (pin "1") (pinfunction "1_1") (pintype "passive"))
      (node (ref "R65") (pin "2") (pinfunction "2_2") (pintype "passive"))
      (node (ref "R66") (pin "1") (pinfunction "1_1") (pintype "passive"))
    )
    (net (code "32") (name "Net-(C84-Pad2)") (class "Default")
      (node (ref "C84") (pin "2") (pinfunction "2_2") (pintype "passive"))
      (node (ref "R62") (pin "1") (pinfunction "1_1") (pintype "passive"))
    )
    (net (code "33") (name "Net-(C86-Pad1)") (class "Default")
      (node (ref "C86") (pin "1") (pinfunction "1_1") (pintype "passive"))
      (node (ref "R67") (pin "2") (pinfunction "2_2") (pintype "passive"))
    )
    (net (code "34") (name "Net-(C87-Pad2)") (class "Default")
      (node (ref "C87") (pin "2") (pinfunction "2_2") (pintype "passive"))
      (node (ref "R71") (pin "2") (pinfunction "2_2") (pintype "passive"))
      (node (ref "R72") (pin "1") (pinfunction "1_1") (pintype "passive"))
    )
    (net (code "35") (name "Net-(C89-Pad1)") (class "Default")
      (node (ref "C89") (pin "1") (pinfunction "1_1") (pintype "passive"))
      (node (ref "R77") (pin "1") (pinfunction "1_1") (pintype "passive"))
      (node (ref "R81") (pin "2") (pinfunction "2_2") (pintype "passive"))
      (node (ref "R82") (pin "1") (pinfunction "1_1") (pintype "passive"))
    )
    (net (code "36") (name "Net-(C89-Pad2)") (class "Default")
      (node (ref "C89") (pin "2") (pinfunction "2_2") (pintype "passive"))
      (node (ref "R78") (pin "1") (pinfunction "1_1") (pintype "passive"))
    )
    (net (code "37") (name "Net-(C91-Pad1)") (class "Default")
      (node (ref "C91") (pin "1") (pinfunction "1_1") (pintype "passive"))
      (node (ref "R83") (pin "2") (pinfunction "2_2") (pintype "passive"))
    )
    (net (code "38") (name "Net-(C92-Pad2)") (class "Default")
      (node (ref "C92") (pin "2") (pinfunction "2_2") (pintype "passive"))
      (node (ref "R89") (pin "2") (pinfunction "2_2") (pintype "passive"))
      (node (ref "R90") (pin "1") (pinfunction "1_1") (pintype "passive"))
    )
    (net (code "39") (name "Net-(D19-C)") (class "Default")
      (node (ref "D19") (pin "3") (pinfunction "C_3") (pintype "passive"))
      (node (ref "R57") (pin "1") (pinfunction "1_1") (pintype "passive"))
      (node (ref "R58") (pin "1") (pinfunction "1_1") (pintype "passive"))
      (node (ref "R60") (pin "2") (pinfunction "2_2") (pintype "passive"))
    )
    (net (code "40") (name "Net-(D20-C)") (class "Default")
      (node (ref "C85") (pin "2") (pinfunction "2_2") (pintype "passive"))
      (node (ref "C86") (pin "2") (pinfunction "2_2") (pintype "passive"))
      (node (ref "D20") (pin "1") (pinfunction "C_1") (pintype "passive"))
      (node (ref "TP1") (pin "1") (pinfunction "1_1") (pintype "passive"))
      (node (ref "U7") (pin "1") (pinfunction "OUT1_1") (pintype "output"))
    )
    (net (code "41") (name "Net-(D21-C)") (class "Default")
      (node (ref "C90") (pin "2") (pinfunction "2_2") (pintype "passive"))
      (node (ref "C91") (pin "2") (pinfunction "2_2") (pintype "passive"))
      (node (ref "D21") (pin "1") (pinfunction "C_1") (pintype "passive"))
      (node (ref "TP5") (pin "1") (pinfunction "1_1") (pintype "passive"))
      (node (ref "U7") (pin "7") (pinfunction "OUT2_7") (pintype "output"))
    )
    (net (code "42") (name "Net-(Q6-D)") (class "Default")
      (node (ref "C27") (pin "1") (pinfunction "1_1") (pintype "passive"))
      (node (ref "C28") (pin "1") (pinfunction "1_1") (pintype "passive"))
      (node (ref "Q6") (pin "3") (pinfunction "D_3") (pintype "passive"))
      (node (ref "U4") (pin "5") (pinfunction "SS/EN_5") (pintype "input"))
    )
    (net (code "43") (name "Net-(Q6-G)") (class "Default")
      (node (ref "Q6") (pin "1") (pinfunction "G_1") (pintype "passive"))
      (node (ref "Q7") (pin "3") (pinfunction "D_3") (pintype "passive"))
      (node (ref "R51") (pin "2") (pinfunction "2_2") (pintype "passive"))
      (node (ref "R52") (pin "1") (pinfunction "1_1") (pintype "passive"))
    )
    (net (code "44") (name "Net-(Q7-G)") (class "Default")
      (node (ref "C29") (pin "1") (pinfunction "1_1") (pintype "passive"))
      (node (ref "Q7") (pin "1") (pinfunction "G_1") (pintype "passive"))
      (node (ref "R53") (pin "2") (pinfunction "2_2") (pintype "passive"))
      (node (ref "R54") (pin "1") (pinfunction "1_1") (pintype "passive"))
    )
    (net (code "45") (name "Net-(Q9-D)") (class "Default")
      (node (ref "Q9") (pin "3") (pinfunction "D_3") (pintype "passive"))
      (node (ref "R70") (pin "2") (pinfunction "2_2") (pintype "passive"))
      (node (ref "R71") (pin "1") (pinfunction "1_1") (pintype "passive"))
    )
    (net (code "46") (name "Net-(Q9-G)") (class "Default")
      (node (ref "Q9") (pin "1") (pinfunction "G_1") (pintype "passive"))
      (node (ref "R74") (pin "2") (pinfunction "2_2") (pintype "passive"))
      (node (ref "R75") (pin "2") (pinfunction "2_2") (pintype "passive"))
      (node (ref "R76") (pin "2") (pinfunction "2_2") (pintype "passive"))
    )
    (net (code "47") (name "Net-(Q10-D)") (class "Default")
      (node (ref "Q10") (pin "3") (pinfunction "D_3") (pintype "passive"))
      (node (ref "R88") (pin "2") (pinfunction "2_2") (pintype "passive"))
      (node (ref "R89") (pin "1") (pinfunction "1_1") (pintype "passive"))
    )
    (net (code "48") (name "Net-(Q10-G)") (class "Default")
      (node (ref "Q10") (pin "1") (pinfunction "G_1") (pintype "passive"))
      (node (ref "R92") (pin "2") (pinfunction "2_2") (pintype "passive"))
      (node (ref "R94") (pin "2") (pinfunction "2_2") (pintype "passive"))
      (node (ref "R95") (pin "2") (pinfunction "2_2") (pintype "passive"))
    )
    (net (code "49") (name "Net-(R3-Pad2)") (class "Default")
      (node (ref "R3") (pin "2") (pinfunction "2_2") (pintype "passive"))
      (node (ref "R33") (pin "1") (pinfunction "1_1") (pintype "passive"))
      (node (ref "R34") (pin "1") (pinfunction "1_1") (pintype "passive"))
      (node (ref "R38") (pin "1") (pinfunction "1_1") (pintype "passive"))
    )
    (net (code "50") (name "Net-(R39-Pad2)") (class "Default")
      (node (ref "R39") (pin "2") (pinfunction "2_2") (pintype "passive"))
      (node (ref "R42") (pin "1") (pinfunction "1_1") (pintype "passive"))
      (node (ref "SB20") (pin "1") (pinfunction "1_1") (pintype "passive"))
    )
    (net (code "51") (name "Net-(R64-Pad2)") (class "Default")
      (node (ref "R64") (pin "2") (pinfunction "2_2") (pintype "passive"))
      (node (ref "R65") (pin "1") (pinfunction "1_1") (pintype "passive"))
      (node (ref "TP3") (pin "1") (pinfunction "1_1") (pintype "passive"))
    )
    (net (code "52") (name "Net-(R68-Pad2)") (class "Default")
      (node (ref "R68") (pin "2") (pinfunction "2_2") (pintype "passive"))
      (node (ref "R69") (pin "1") (pinfunction "1_1") (pintype "passive"))
    )
    (net (code "53") (name "Net-(R80-Pad2)") (class "Default")
      (node (ref "R80") (pin "2") (pinfunction "2_2") (pintype "passive"))
      (node (ref "R81") (pin "1") (pinfunction "1_1") (pintype "passive"))
      (node (ref "TP7") (pin "1") (pinfunction "1_1") (pintype "passive"))
    )
    (net (code "54") (name "Net-(R85-Pad2)") (class "Default")
      (node (ref "R85") (pin "2") (pinfunction "2_2") (pintype "passive"))
      (node (ref "R86") (pin "1") (pinfunction "1_1") (pintype "passive"))
    )
    (net (code "55") (name "Net-(U4-ADEL)") (class "Default")
      (node (ref "R33") (pin "2") (pinfunction "2_2") (pintype "passive"))
      (node (ref "R40") (pin "1") (pinfunction "1_1") (pintype "passive"))
      (node (ref "U4") (pin "14") (pinfunction "ADEL_14") (pintype "input"))
    )
    (net (code "56") (name "Net-(U4-ADELEF)") (class "Default")
      (node (ref "R34") (pin "2") (pinfunction "2_2") (pintype "passive"))
      (node (ref "R41") (pin "1") (pinfunction "1_1") (pintype "passive"))
      (node (ref "U4") (pin "13") (pinfunction "ADELEF_13") (pintype "input"))
    )
    (net (code "57") (name "Net-(U4-COMP)") (class "Default")
      (node (ref "C12") (pin "1") (pinfunction "1_1") (pintype "passive"))
      (node (ref "C13") (pin "1") (pinfunction "1_1") (pintype "passive"))
      (node (ref "SB22") (pin "2") (pinfunction "2_2") (pintype "passive"))
      (node (ref "U4") (pin "4") (pinfunction "COMP_4") (pintype "bidirectional"))
    )
    (net (code "58") (name "Net-(U4-CS)") (class "Default")
      (node (ref "C14") (pin "1") (pinfunction "1_1") (pintype "passive"))
      (node (ref "C83") (pin "1") (pinfunction "1_1") (pintype "passive"))
      (node (ref "R38") (pin "2") (pinfunction "2_2") (pintype "passive"))
      (node (ref "R58") (pin "2") (pinfunction "2_2") (pintype "passive"))
      (node (ref "R59") (pin "2") (pinfunction "2_2") (pintype "passive"))
      (node (ref "U4") (pin "15") (pinfunction "CS_15") (pintype "input"))
    )
    (net (code "59") (name "Net-(U4-DCM)") (class "Default")
      (node (ref "R47") (pin "1") (pinfunction "1_1") (pintype "passive"))
      (node (ref "R6") (pin "2") (pinfunction "2_2") (pintype "passive"))
      (node (ref "U4") (pin "12") (pinfunction "DCM_12") (pintype "input"))
    )
    (net (code "60") (name "Net-(U4-DELAB)") (class "Default")
      (node (ref "R35") (pin "1") (pinfunction "1_1") (pintype "passive"))
      (node (ref "U4") (pin "6") (pinfunction "DELAB_6") (pintype "input"))
    )
    (net (code "61") (name "Net-(U4-DELCD)") (class "Default")
      (node (ref "R36") (pin "1") (pinfunction "1_1") (pintype "passive"))
      (node (ref "U4") (pin "7") (pinfunction "DELCD_7") (pintype "input"))
    )
    (net (code "62") (name "Net-(U4-DELEF)") (class "Default")
      (node (ref "R37") (pin "1") (pinfunction "1_1") (pintype "passive"))
      (node (ref "U4") (pin "8") (pinfunction "DELEF_8") (pintype "input"))
    )
    (net (code "63") (name "Net-(U4-RSUM)") (class "Default")
      (node (ref "R43") (pin "1") (pinfunction "1_1") (pintype "passive"))
      (node (ref "U4") (pin "11") (pinfunction "RSUM_11") (pintype "input"))
    )
    (net (code "64") (name "Net-(U4-RT)") (class "Default")
      (node (ref "R48") (pin "1") (pinfunction "1_1") (pintype "passive"))
      (node (ref "U4") (pin "10") (pinfunction "RT_10") (pintype "input"))
    )
    (net (code "65") (name "Net-(U4-SYNC)") (class "Default")
      (node (ref "SB21") (pin "2") (pinfunction "2_2") (pintype "passive"))
      (node (ref "U4") (pin "16") (pinfunction "SYNC_16") (pintype "bidirectional"))
    )
    (net (code "66") (name "Net-(U4-TMIN)") (class "Default")
      (node (ref "R44") (pin "1") (pinfunction "1_1") (pintype "passive"))
      (node (ref "U4") (pin "9") (pinfunction "TMIN_9") (pintype "input"))
    )
    (net (code "67") (name "Net-(U6A-REF)") (class "Default")
      (node (ref "R87") (pin "1") (pinfunction "1_1") (pintype "passive"))
      (node (ref "R93") (pin "2") (pinfunction "2_2") (pintype "passive"))
      (node (ref "U6") (pin "4") (pinfunction "REF_4") (pintype "input"))
    )
    (net (code "68") (name "Net-(U7A-IN1+)") (class "Default")
      (node (ref "C88") (pin "1") (pinfunction "1_1") (pintype "passive"))
      (node (ref "R69") (pin "2") (pinfunction "2_2") (pintype "passive"))
      (node (ref "R72") (pin "2") (pinfunction "2_2") (pintype "passive"))
      (node (ref "R73") (pin "2") (pinfunction "2_2") (pintype "passive"))
      (node (ref "U7") (pin "3") (pinfunction "IN1+_3") (pintype "input"))
    )
    (net (code "69") (name "Net-(U7A-IN1-)") (class "Default")
      (node (ref "C85") (pin "1") (pinfunction "1_1") (pintype "passive"))
      (node (ref "R61") (pin "2") (pinfunction "2_2") (pintype "passive"))
      (node (ref "R62") (pin "2") (pinfunction "2_2") (pintype "passive"))
      (node (ref "R63") (pin "2") (pinfunction "2_2") (pintype "passive"))
      (node (ref "R66") (pin "2") (pinfunction "2_2") (pintype "passive"))
      (node (ref "R67") (pin "1") (pinfunction "1_1") (pintype "passive"))
      (node (ref "U7") (pin "2") (pinfunction "IN1-_2") (pintype "input"))
    )
    (net (code "70") (name "Net-(U7B-IN2+)") (class "Default")
      (node (ref "C93") (pin "1") (pinfunction "1_1") (pintype "passive"))
      (node (ref "R86") (pin "2") (pinfunction "2_2") (pintype "passive"))
      (node (ref "R90") (pin "2") (pinfunction "2_2") (pintype "passive"))
      (node (ref "R91") (pin "2") (pinfunction "2_2") (pintype "passive"))
      (node (ref "U7") (pin "5") (pinfunction "IN2+_5") (pintype "input"))
    )
    (net (code "71") (name "Net-(U7B-IN2-)") (class "Default")
      (node (ref "C90") (pin "1") (pinfunction "1_1") (pintype "passive"))
      (node (ref "R78") (pin "2") (pinfunction "2_2") (pintype "passive"))
      (node (ref "R79") (pin "1") (pinfunction "1_1") (pintype "passive"))
      (node (ref "R82") (pin "2") (pinfunction "2_2") (pintype "passive"))
      (node (ref "R83") (pin "1") (pinfunction "1_1") (pintype "passive"))
      (node (ref "U7") (pin "6") (pinfunction "IN2-_6") (pintype "input"))
    )
    (net (code "72") (name "OPAMP_COMP_VCC") (class "Default")
      (node (ref "C97") (pin "1") (pinfunction "1_1") (pintype "passive"))
      (node (ref "C98") (pin "1") (pinfunction "1_1") (pintype "passive"))
      (node (ref "C99") (pin "2") (pinfunction "P_2") (pintype "passive"))
      (node (ref "U7") (pin "8") (pinfunction "VDD_8") (pintype "power_in"))
    )
    (net (code "73") (name "OPAMP_COMP_VSS") (class "Default")
      (node (ref "C97") (pin "2") (pinfunction "2_2") (pintype "passive"))
      (node (ref "C98") (pin "2") (pinfunction "2_2") (pintype "passive"))
      (node (ref "C99") (pin "1") (pinfunction "N_1") (pintype "passive"))
      (node (ref "U7") (pin "4") (pinfunction "GND_4") (pintype "power_in"))
    )
    (net (code "74") (name "VREF_28951") (class "Default")
      (node (ref "C10") (pin "1") (pinfunction "1_1") (pintype "passive"))
      (node (ref "C11") (pin "1") (pinfunction "1_1") (pintype "passive"))
      (node (ref "R3") (pin "1") (pinfunction "1_1") (pintype "passive"))
      (node (ref "R39") (pin "1") (pinfunction "1_1") (pintype "passive"))
      (node (ref "R48") (pin "2") (pinfunction "2_2") (pintype "passive"))
      (node (ref "R5") (pin "2") (pinfunction "2_2") (pintype "passive"))
      (node (ref "R6") (pin "1") (pinfunction "1_1") (pintype "passive"))
      (node (ref "U4") (pin "1") (pinfunction "VREF_1") (pintype "output"))
    )
    (net (code "75") (name "unconnected-(D19-NC-Pad2)") (class "Default")
      (node (ref "D19") (pin "2") (pinfunction "NC_2") (pintype "passive+no_connect"))
    )
    (net (code "76") (name "unconnected-(U6B-NC-Pad1)") (class "Default")
      (node (ref "U6") (pin "1") (pinfunction "NC_1") (pintype "passive+no_connect"))
    )
    (net (code "77") (name "unconnected-(U6B-NC-Pad2)") (class "Default")
      (node (ref "U6") (pin "2") (pinfunction "NC_2") (pintype "passive+no_connect"))
    )
  )
)
